# LSM.net
KiCad netlist of a schematic drawn in Altium Designer
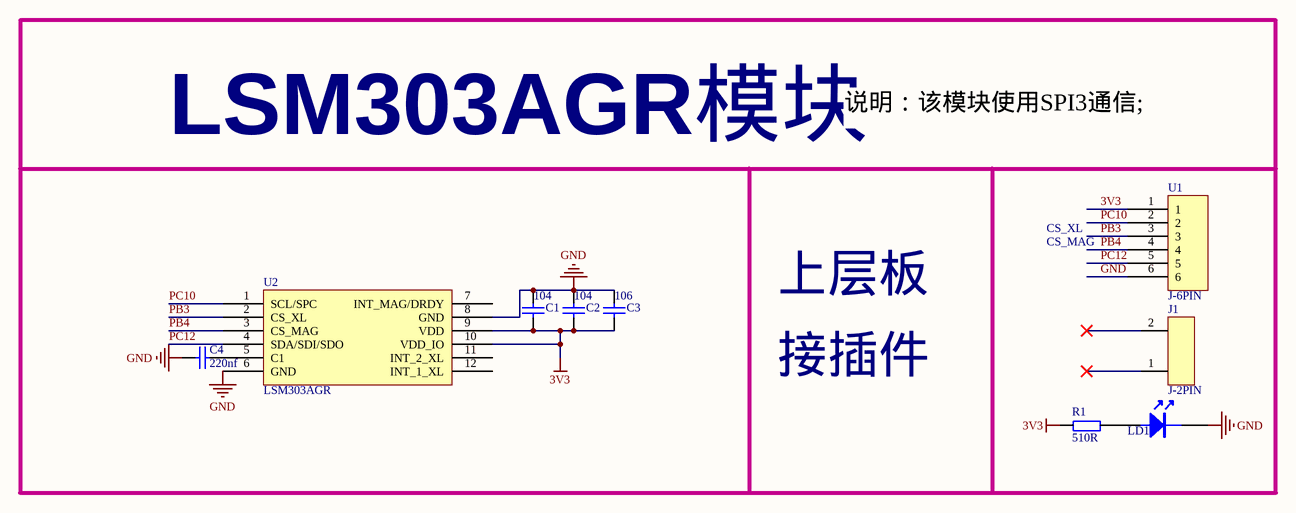
[diagram p0: LSM模块.SchDoc]

(export (version "E")
  (design (tool "Eeschema 10.0.6"))
  (components
    (comp (ref "C1")
      (value "104")
      (footprint "C-0805c")
      (description "Capacitor")
      (fields (field (name "PUBLISHER") "Altium Limited"))
      (libsource (lib "Miscellaneous Devices") (part "C-贴片电容"))
    )
    (comp (ref "C2")
      (value "104")
      (footprint "C-0805c")
      (description "Capacitor")
      (fields (field (name "PUBLISHER") "Altium Limited"))
      (libsource (lib "Miscellaneous Devices") (part "C-贴片电容"))
    )
    (comp (ref "C3")
      (value "106")
      (footprint "C-0805C")
      (description "Capacitor")
      (fields (field (name "PUBLISHER") "Altium Limited"))
      (libsource (lib "Miscellaneous Devices") (part "C-贴片电容"))
    )
    (comp (ref "C4")
      (value "220nf")
      (footprint "C-0805C")
      (description "Capacitor")
      (fields (field (name "PUBLISHER") "Altium Limited"))
      (libsource (lib "Miscellaneous Devices") (part "C-贴片电容"))
    )
    (comp (ref "J1")
      (value "J-2PIN")
      (footprint "HDR1X2")
      (description "SOCKET")
      (libsource (lib "ACTION原理图库") (part "J-2PIN"))
    )
    (comp (ref "LD1") (value "~") (footprint "D-0603D") (libsource (lib "ACTION原理图库") (part "LED")))
    (comp (ref "R1")
      (value "510R")
      (footprint "R-0603R")
      (description "RES, 10K, 5%, 0.1 W, 0603")
      (libsource (lib "ACTION原理图库") (part "Resistor"))
    )
    (comp (ref "U1") (value "J-6PIN") (footprint "LSM底座") (libsource (lib "ACTION原理图库") (part "J-6PIN")))
    (comp (ref "U2")
      (value "LSM303AGR")
      (footprint "LSM电子罗盘")
      (description "e-compass")
      (libsource (lib "陀螺仪元件库") (part "LSM303AGR"))
    )
  )
  (nets
    (net (code "1") (name "/PB3") (class "Default")
      (node (ref "U1") (pin "3") (pinfunction "3_3") (pintype "passive"))
      (node (ref "U2") (pin "2") (pinfunction "CS_XL_2") (pintype "passive"))
    )
    (net (code "2") (name "/PB4") (class "Default")
      (node (ref "U1") (pin "4") (pinfunction "4_4") (pintype "passive"))
      (node (ref "U2") (pin "3") (pinfunction "CS_MAG_3") (pintype "passive"))
    )
    (net (code "3") (name "/PC10") (class "Default")
      (node (ref "U1") (pin "2") (pinfunction "2_2") (pintype "passive"))
      (node (ref "U2") (pin "1") (pinfunction "SCL/SPC_1") (pintype "passive"))
    )
    (net (code "4") (name "/PC12") (class "Default")
      (node (ref "U1") (pin "5") (pinfunction "5_5") (pintype "passive"))
      (node (ref "U2") (pin "4") (pinfunction "SDA/SDI/SDO_4") (pintype "passive"))
    )
    (net (code "5") (name "3V3") (class "Default")
      (node (ref "C1") (pin "2") (pinfunction "2_2") (pintype "passive"))
      (node (ref "C2") (pin "2") (pinfunction "2_2") (pintype "passive"))
      (node (ref "C3") (pin "2") (pinfunction "2_2") (pintype "passive"))
      (node (ref "R1") (pin "1") (pintype "passive"))
      (node (ref "U1") (pin "1") (pinfunction "1_1") (pintype "passive"))
      (node (ref "U2") (pin "10") (pinfunction "VDD_IO_10") (pintype "passive"))
      (node (ref "U2") (pin "9") (pinfunction "VDD_9") (pintype "passive"))
    )
    (net (code "6") (name "GND") (class "Default")
      (node (ref "C1") (pin "1") (pinfunction "1_1") (pintype "passive"))
      (node (ref "C2") (pin "1") (pinfunction "1_1") (pintype "passive"))
      (node (ref "C3") (pin "1") (pinfunction "1_1") (pintype "passive"))
      (node (ref "C4") (pin "2") (pinfunction "2_2") (pintype "passive"))
      (node (ref "LD1") (pin "2") (pinfunction "2_2") (pintype "passive"))
      (node (ref "U1") (pin "6") (pinfunction "6_6") (pintype "passive"))
      (node (ref "U2") (pin "6") (pinfunction "GND_6") (pintype "passive"))
      (node (ref "U2") (pin "8") (pinfunction "GND_8") (pintype "passive"))
    )
    (net (code "7") (name "Net-(LD1-Pad1)") (class "Default")
      (node (ref "LD1") (pin "1") (pinfunction "1_1") (pintype "passive"))
      (node (ref "R1") (pin "2") (pintype "passive"))
    )
    (net (code "8") (name "Net-(U2-C1)") (class "Default")
      (node (ref "C4") (pin "1") (pinfunction "1_1") (pintype "passive"))
      (node (ref "U2") (pin "5") (pinfunction "C1_5") (pintype "passive"))
    )
    (net (code "9") (name "unconnected-(J1-Pad1)") (class "Default")
      (node (ref "J1") (pin "1") (pinfunction "1_1") (pintype "passive+no_connect"))
    )
    (net (code "10") (name "unconnected-(J1-Pad2)") (class "Default")
      (node (ref "J1") (pin "2") (pinfunction "2_2") (pintype "passive+no_connect"))
    )
    (net (code "11") (name "unconnected-(U2-INT_1_XL-Pad12)") (class "Default")
      (node (ref "U2") (pin "12") (pinfunction "INT_1_XL_12") (pintype "passive"))
    )
    (net (code "12") (name "unconnected-(U2-INT_2_XL-Pad11)") (class "Default")
      (node (ref "U2") (pin "11") (pinfunction "INT_2_XL_11") (pintype "passive"))
    )
    (net (code "13") (name "unconnected-(U2-INT_MAG{slash}DRDY-Pad7)") (class "Default")
      (node (ref "U2") (pin "7") (pinfunction "INT_MAG/DRDY_7") (pintype "passive"))
    )
  )
)
